# Connectors.net
KiCad netlist of a schematic drawn in Altium Designer
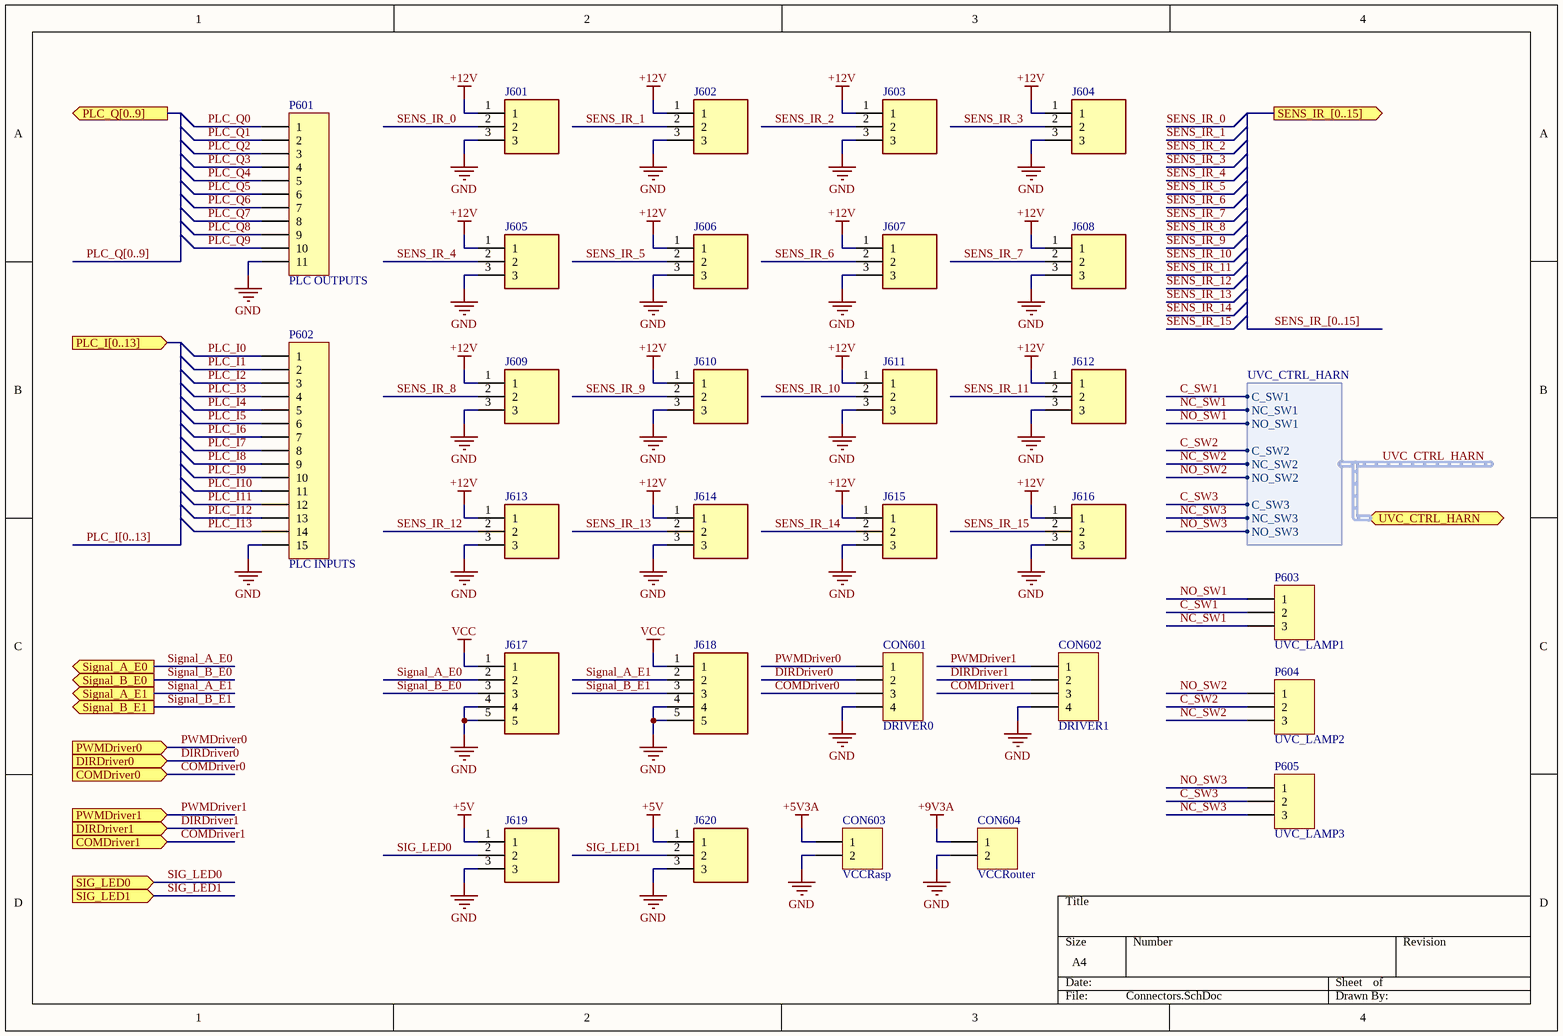
[diagram p0: Connectors.SchDoc]

(export (version "E")
  (design (tool "Eeschema 10.0.6"))
  (components
    (comp (ref "CON601")
      (value "Header PW4 - Recto")
      (footprint "PW4 - Recto")
      (description "Header PW - paso 0.156\"")
      (fields (field (name "VALOR") "DRIVER0"))
      (libsource (lib "RUF-Conectores") (part "Header PW4 - Recto"))
    )
    (comp (ref "CON602")
      (value "Header PW4 - Recto")
      (footprint "PW4 - Recto")
      (description "Header PW - paso 0.156\"")
      (fields (field (name "VALOR") "DRIVER1"))
      (libsource (lib "RUF-Conectores") (part "Header PW4 - Recto"))
    )
    (comp (ref "CON603")
      (value "Header PW2 - Recto")
      (footprint "PW2 - Recto")
      (description "Header PW - paso 0.156\"")
      (fields (field (name "VALOR") "VCCRasp"))
      (libsource (lib "RUF-Conectores") (part "Header PW2 - Recto"))
    )
    (comp (ref "CON604")
      (value "Header PW2 - Recto")
      (footprint "PW2 - Recto")
      (description "Header PW - paso 0.156\"")
      (fields (field (name "VALOR") "VCCRouter"))
      (libsource (lib "RUF-Conectores") (part "Header PW2 - Recto"))
    )
    (comp (ref "J601")
      (value "TBL002A-350-03GR-2OR")
      (footprint "CUI_TBL002A-350-03GR-2OR")
      (description "1~24 Poles, Screwless, 45°, 3.50 Pitch, 24~20 (AWG), Terminal Block Connector")
      (fields (field (name "MF") "CUI Devices"))
      (libsource (lib "TBL002A-350-03GR-2OR") (part "TBL002A-350-03GR-2OR"))
    )
    (comp (ref "J602")
      (value "TBL002A-350-03GR-2OR")
      (footprint "CUI_TBL002A-350-03GR-2OR")
      (description "1~24 Poles, Screwless, 45°, 3.50 Pitch, 24~20 (AWG), Terminal Block Connector")
      (fields (field (name "MF") "CUI Devices"))
      (libsource (lib "TBL002A-350-03GR-2OR") (part "TBL002A-350-03GR-2OR"))
    )
    (comp (ref "J603")
      (value "TBL002A-350-03GR-2OR")
      (footprint "CUI_TBL002A-350-03GR-2OR")
      (description "1~24 Poles, Screwless, 45°, 3.50 Pitch, 24~20 (AWG), Terminal Block Connector")
      (fields (field (name "MF") "CUI Devices"))
      (libsource (lib "TBL002A-350-03GR-2OR") (part "TBL002A-350-03GR-2OR"))
    )
    (comp (ref "J604")
      (value "TBL002A-350-03GR-2OR")
      (footprint "CUI_TBL002A-350-03GR-2OR")
      (description "1~24 Poles, Screwless, 45°, 3.50 Pitch, 24~20 (AWG), Terminal Block Connector")
      (fields (field (name "MF") "CUI Devices"))
      (libsource (lib "TBL002A-350-03GR-2OR") (part "TBL002A-350-03GR-2OR"))
    )
    (comp (ref "J605")
      (value "TBL002A-350-03GR-2OR")
      (footprint "CUI_TBL002A-350-03GR-2OR")
      (description "1~24 Poles, Screwless, 45°, 3.50 Pitch, 24~20 (AWG), Terminal Block Connector")
      (fields (field (name "MF") "CUI Devices"))
      (libsource (lib "TBL002A-350-03GR-2OR") (part "TBL002A-350-03GR-2OR"))
    )
    (comp (ref "J606")
      (value "TBL002A-350-03GR-2OR")
      (footprint "CUI_TBL002A-350-03GR-2OR")
      (description "1~24 Poles, Screwless, 45°, 3.50 Pitch, 24~20 (AWG), Terminal Block Connector")
      (fields (field (name "MF") "CUI Devices"))
      (libsource (lib "TBL002A-350-03GR-2OR") (part "TBL002A-350-03GR-2OR"))
    )
    (comp (ref "J607")
      (value "TBL002A-350-03GR-2OR")
      (footprint "CUI_TBL002A-350-03GR-2OR")
      (description "1~24 Poles, Screwless, 45°, 3.50 Pitch, 24~20 (AWG), Terminal Block Connector")
      (fields (field (name "MF") "CUI Devices"))
      (libsource (lib "TBL002A-350-03GR-2OR") (part "TBL002A-350-03GR-2OR"))
    )
    (comp (ref "J608")
      (value "TBL002A-350-03GR-2OR")
      (footprint "CUI_TBL002A-350-03GR-2OR")
      (description "1~24 Poles, Screwless, 45°, 3.50 Pitch, 24~20 (AWG), Terminal Block Connector")
      (fields (field (name "MF") "CUI Devices"))
      (libsource (lib "TBL002A-350-03GR-2OR") (part "TBL002A-350-03GR-2OR"))
    )
    (comp (ref "J609")
      (value "TBL002A-350-03GR-2OR")
      (footprint "CUI_TBL002A-350-03GR-2OR")
      (description "1~24 Poles, Screwless, 45°, 3.50 Pitch, 24~20 (AWG), Terminal Block Connector")
      (fields (field (name "MF") "CUI Devices"))
      (libsource (lib "TBL002A-350-03GR-2OR") (part "TBL002A-350-03GR-2OR"))
    )
    (comp (ref "J610")
      (value "TBL002A-350-03GR-2OR")
      (footprint "CUI_TBL002A-350-03GR-2OR")
      (description "1~24 Poles, Screwless, 45°, 3.50 Pitch, 24~20 (AWG), Terminal Block Connector")
      (fields (field (name "MF") "CUI Devices"))
      (libsource (lib "TBL002A-350-03GR-2OR") (part "TBL002A-350-03GR-2OR"))
    )
    (comp (ref "J611")
      (value "TBL002A-350-03GR-2OR")
      (footprint "CUI_TBL002A-350-03GR-2OR")
      (description "1~24 Poles, Screwless, 45°, 3.50 Pitch, 24~20 (AWG), Terminal Block Connector")
      (fields (field (name "MF") "CUI Devices"))
      (libsource (lib "TBL002A-350-03GR-2OR") (part "TBL002A-350-03GR-2OR"))
    )
    (comp (ref "J612")
      (value "TBL002A-350-03GR-2OR")
      (footprint "CUI_TBL002A-350-03GR-2OR")
      (description "1~24 Poles, Screwless, 45°, 3.50 Pitch, 24~20 (AWG), Terminal Block Connector")
      (fields (field (name "MF") "CUI Devices"))
      (libsource (lib "TBL002A-350-03GR-2OR") (part "TBL002A-350-03GR-2OR"))
    )
    (comp (ref "J613")
      (value "TBL002A-350-03GR-2OR")
      (footprint "CUI_TBL002A-350-03GR-2OR")
      (description "1~24 Poles, Screwless, 45°, 3.50 Pitch, 24~20 (AWG), Terminal Block Connector")
      (fields (field (name "MF") "CUI Devices"))
      (libsource (lib "TBL002A-350-03GR-2OR") (part "TBL002A-350-03GR-2OR"))
    )
    (comp (ref "J614")
      (value "TBL002A-350-03GR-2OR")
      (footprint "CUI_TBL002A-350-03GR-2OR")
      (description "1~24 Poles, Screwless, 45°, 3.50 Pitch, 24~20 (AWG), Terminal Block Connector")
      (fields (field (name "MF") "CUI Devices"))
      (libsource (lib "TBL002A-350-03GR-2OR") (part "TBL002A-350-03GR-2OR"))
    )
    (comp (ref "J615")
      (value "TBL002A-350-03GR-2OR")
      (footprint "CUI_TBL002A-350-03GR-2OR")
      (description "1~24 Poles, Screwless, 45°, 3.50 Pitch, 24~20 (AWG), Terminal Block Connector")
      (fields (field (name "MF") "CUI Devices"))
      (libsource (lib "TBL002A-350-03GR-2OR") (part "TBL002A-350-03GR-2OR"))
    )
    (comp (ref "J616")
      (value "TBL002A-350-03GR-2OR")
      (footprint "CUI_TBL002A-350-03GR-2OR")
      (description "1~24 Poles, Screwless, 45°, 3.50 Pitch, 24~20 (AWG), Terminal Block Connector")
      (fields (field (name "MF") "CUI Devices"))
      (libsource (lib "TBL002A-350-03GR-2OR") (part "TBL002A-350-03GR-2OR"))
    )
    (comp (ref "J617")
      (value "TBL002A-350-05GR-2OR")
      (footprint "CUI_TBL002A-350-05GR-2OR")
      (description "1~24 Poles, Screwless, 45°, 3.50 Pitch, 24~20 (AWG), Terminal Block Connector")
      (fields (field (name "MF") "CUI Devices"))
      (libsource (lib "TBL002A-350-05GR-2OR") (part "TBL002A-350-05GR-2OR"))
    )
    (comp (ref "J618")
      (value "TBL002A-350-05GR-2OR")
      (footprint "CUI_TBL002A-350-05GR-2OR")
      (description "1~24 Poles, Screwless, 45°, 3.50 Pitch, 24~20 (AWG), Terminal Block Connector")
      (fields (field (name "MF") "CUI Devices"))
      (libsource (lib "TBL002A-350-05GR-2OR") (part "TBL002A-350-05GR-2OR"))
    )
    (comp (ref "J619")
      (value "TBL002A-350-03GR-2OR")
      (footprint "CUI_TBL002A-350-03GR-2OR")
      (description "1~24 Poles, Screwless, 45°, 3.50 Pitch, 24~20 (AWG), Terminal Block Connector")
      (fields (field (name "MF") "CUI Devices"))
      (libsource (lib "TBL002A-350-03GR-2OR") (part "TBL002A-350-03GR-2OR"))
    )
    (comp (ref "J620")
      (value "TBL002A-350-03GR-2OR")
      (footprint "CUI_TBL002A-350-03GR-2OR")
      (description "1~24 Poles, Screwless, 45°, 3.50 Pitch, 24~20 (AWG), Terminal Block Connector")
      (fields (field (name "MF") "CUI Devices"))
      (libsource (lib "TBL002A-350-03GR-2OR") (part "TBL002A-350-03GR-2OR"))
    )
    (comp (ref "P601")
      (value "PLC OUTPUTS")
      (footprint "SPTAF_1/15-3.5-EL_11POS")
      (description "Header, 11-Pin")
      (fields (field (name "PUBLISHER") "Altium Limited"))
      (libsource (lib "Miscellaneous Connectors") (part "Header 11"))
    )
    (comp (ref "P602")
      (value "PLC INPUTS")
      (footprint "SPTAF_1/15-3.5-EL_15POS")
      (description "Header, 15-Pin")
      (fields (field (name "PUBLISHER") "Altium Limited"))
      (libsource (lib "Miscellaneous Connectors") (part "Header 15"))
    )
    (comp (ref "P603")
      (value "UVC_LAMP1")
      (footprint "Terminal_3way_508")
      (description "Header, 3-Pin")
      (fields (field (name "PUBLISHER") "Altium Limited"))
      (libsource (lib "Miscellaneous Connectors") (part "Header 3"))
    )
    (comp (ref "P604")
      (value "UVC_LAMP2")
      (footprint "Terminal_3way_508")
      (description "Header, 3-Pin")
      (fields (field (name "PUBLISHER") "Altium Limited"))
      (libsource (lib "Miscellaneous Connectors") (part "Header 3"))
    )
    (comp (ref "P605")
      (value "UVC_LAMP3")
      (footprint "Terminal_3way_508")
      (description "Header, 3-Pin")
      (fields (field (name "PUBLISHER") "Altium Limited"))
      (libsource (lib "Miscellaneous Connectors") (part "Header 3"))
    )
  )
  (nets
    (net (code "2") (name "+5V") (class "Default")
      (node (ref "J619") (pin "1") (pinfunction "1_1") (pintype "passive"))
      (node (ref "J620") (pin "1") (pinfunction "1_1") (pintype "passive"))
    )
    (net (code "3") (name "+5V3A") (class "Default")
      (node (ref "CON603") (pin "1") (pinfunction "1_1") (pintype "passive"))
    )
    (net (code "4") (name "+9V3A") (class "Default")
      (node (ref "CON604") (pin "1") (pinfunction "1_1") (pintype "passive"))
    )
    (net (code "5") (name "+12V") (class "Default")
      (node (ref "J601") (pin "1") (pinfunction "1_1") (pintype "passive"))
      (node (ref "J602") (pin "1") (pinfunction "1_1") (pintype "passive"))
      (node (ref "J603") (pin "1") (pinfunction "1_1") (pintype "passive"))
      (node (ref "J604") (pin "1") (pinfunction "1_1") (pintype "passive"))
      (node (ref "J605") (pin "1") (pinfunction "1_1") (pintype "passive"))
      (node (ref "J606") (pin "1") (pinfunction "1_1") (pintype "passive"))
      (node (ref "J607") (pin "1") (pinfunction "1_1") (pintype "passive"))
      (node (ref "J608") (pin "1") (pinfunction "1_1") (pintype "passive"))
      (node (ref "J609") (pin "1") (pinfunction "1_1") (pintype "passive"))
      (node (ref "J610") (pin "1") (pinfunction "1_1") (pintype "passive"))
      (node (ref "J611") (pin "1") (pinfunction "1_1") (pintype "passive"))
      (node (ref "J612") (pin "1") (pinfunction "1_1") (pintype "passive"))
      (node (ref "J613") (pin "1") (pinfunction "1_1") (pintype "passive"))
      (node (ref "J614") (pin "1") (pinfunction "1_1") (pintype "passive"))
      (node (ref "J615") (pin "1") (pinfunction "1_1") (pintype "passive"))
      (node (ref "J616") (pin "1") (pinfunction "1_1") (pintype "passive"))
    )
    (net (code "6") (name "/COMDriver0") (class "Default")
      (node (ref "CON601") (pin "3") (pinfunction "3_3") (pintype "passive"))
    )
    (net (code "7") (name "/COMDriver1") (class "Default")
      (node (ref "CON602") (pin "3") (pinfunction "3_3") (pintype "passive"))
    )
    (net (code "8") (name "/C_SW1") (class "Default")
      (node (ref "P603") (pin "2") (pinfunction "2_2") (pintype "passive"))
    )
    (net (code "9") (name "/C_SW2") (class "Default")
      (node (ref "P604") (pin "2") (pinfunction "2_2") (pintype "passive"))
    )
    (net (code "10") (name "/C_SW3") (class "Default")
      (node (ref "P605") (pin "2") (pinfunction "2_2") (pintype "passive"))
    )
    (net (code "11") (name "/DIRDriver0") (class "Default")
      (node (ref "CON601") (pin "2") (pinfunction "2_2") (pintype "passive"))
    )
    (net (code "12") (name "/DIRDriver1") (class "Default")
      (node (ref "CON602") (pin "2") (pinfunction "2_2") (pintype "passive"))
    )
    (net (code "13") (name "/NC_SW1") (class "Default")
      (node (ref "P603") (pin "3") (pinfunction "3_3") (pintype "passive"))
    )
    (net (code "14") (name "/NC_SW2") (class "Default")
      (node (ref "P604") (pin "3") (pinfunction "3_3") (pintype "passive"))
    )
    (net (code "15") (name "/NC_SW3") (class "Default")
      (node (ref "P605") (pin "3") (pinfunction "3_3") (pintype "passive"))
    )
    (net (code "16") (name "/NO_SW1") (class "Default")
      (node (ref "P603") (pin "1") (pinfunction "1_1") (pintype "passive"))
    )
    (net (code "17") (name "/NO_SW2") (class "Default")
      (node (ref "P604") (pin "1") (pinfunction "1_1") (pintype "passive"))
    )
    (net (code "18") (name "/NO_SW3") (class "Default")
      (node (ref "P605") (pin "1") (pinfunction "1_1") (pintype "passive"))
    )
    (net (code "19") (name "/PLC_I0") (class "Default")
      (node (ref "P602") (pin "1") (pinfunction "1_1") (pintype "passive"))
    )
    (net (code "20") (name "/PLC_I1") (class "Default")
      (node (ref "P602") (pin "2") (pinfunction "2_2") (pintype "passive"))
    )
    (net (code "21") (name "/PLC_I2") (class "Default")
      (node (ref "P602") (pin "3") (pinfunction "3_3") (pintype "passive"))
    )
    (net (code "22") (name "/PLC_I3") (class "Default")
      (node (ref "P602") (pin "4") (pinfunction "4_4") (pintype "passive"))
    )
    (net (code "23") (name "/PLC_I4") (class "Default")
      (node (ref "P602") (pin "5") (pinfunction "5_5") (pintype "passive"))
    )
    (net (code "24") (name "/PLC_I5") (class "Default")
      (node (ref "P602") (pin "6") (pinfunction "6_6") (pintype "passive"))
    )
    (net (code "25") (name "/PLC_I6") (class "Default")
      (node (ref "P602") (pin "7") (pinfunction "7_7") (pintype "passive"))
    )
    (net (code "26") (name "/PLC_I7") (class "Default")
      (node (ref "P602") (pin "8") (pinfunction "8_8") (pintype "passive"))
    )
    (net (code "27") (name "/PLC_I8") (class "Default")
      (node (ref "P602") (pin "9") (pinfunction "9_9") (pintype "passive"))
    )
    (net (code "28") (name "/PLC_I9") (class "Default")
      (node (ref "P602") (pin "10") (pinfunction "10_10") (pintype "passive"))
    )
    (net (code "29") (name "/PLC_I10") (class "Default")
      (node (ref "P602") (pin "11") (pinfunction "11_11") (pintype "passive"))
    )
    (net (code "30") (name "/PLC_I11") (class "Default")
      (node (ref "P602") (pin "12") (pinfunction "12_12") (pintype "passive"))
    )
    (net (code "31") (name "/PLC_I12") (class "Default")
      (node (ref "P602") (pin "13") (pinfunction "13_13") (pintype "passive"))
    )
    (net (code "32") (name "/PLC_I13") (class "Default")
      (node (ref "P602") (pin "14") (pinfunction "14_14") (pintype "passive"))
    )
    (net (code "34") (name "/PLC_Q0") (class "Default")
      (node (ref "P601") (pin "1") (pinfunction "1_1") (pintype "passive"))
    )
    (net (code "35") (name "/PLC_Q1") (class "Default")
      (node (ref "P601") (pin "2") (pinfunction "2_2") (pintype "passive"))
    )
    (net (code "36") (name "/PLC_Q2") (class "Default")
      (node (ref "P601") (pin "3") (pinfunction "3_3") (pintype "passive"))
    )
    (net (code "37") (name "/PLC_Q3") (class "Default")
      (node (ref "P601") (pin "4") (pinfunction "4_4") (pintype "passive"))
    )
    (net (code "38") (name "/PLC_Q4") (class "Default")
      (node (ref "P601") (pin "5") (pinfunction "5_5") (pintype "passive"))
    )
    (net (code "39") (name "/PLC_Q5") (class "Default")
      (node (ref "P601") (pin "6") (pinfunction "6_6") (pintype "passive"))
    )
    (net (code "40") (name "/PLC_Q6") (class "Default")
      (node (ref "P601") (pin "7") (pinfunction "7_7") (pintype "passive"))
    )
    (net (code "41") (name "/PLC_Q7") (class "Default")
      (node (ref "P601") (pin "8") (pinfunction "8_8") (pintype "passive"))
    )
    (net (code "42") (name "/PLC_Q8") (class "Default")
      (node (ref "P601") (pin "9") (pinfunction "9_9") (pintype "passive"))
    )
    (net (code "43") (name "/PLC_Q9") (class "Default")
      (node (ref "P601") (pin "10") (pinfunction "10_10") (pintype "passive"))
    )
    (net (code "45") (name "/PWMDriver0") (class "Default")
      (node (ref "CON601") (pin "1") (pinfunction "1_1") (pintype "passive"))
    )
    (net (code "46") (name "/PWMDriver1") (class "Default")
      (node (ref "CON602") (pin "1") (pinfunction "1_1") (pintype "passive"))
    )
    (net (code "47") (name "/SENS_IR_0") (class "Default")
      (node (ref "J601") (pin "2") (pinfunction "2_2") (pintype "passive"))
    )
    (net (code "48") (name "/SENS_IR_1") (class "Default")
      (node (ref "J602") (pin "2") (pinfunction "2_2") (pintype "passive"))
    )
    (net (code "49") (name "/SENS_IR_2") (class "Default")
      (node (ref "J603") (pin "2") (pinfunction "2_2") (pintype "passive"))
    )
    (net (code "50") (name "/SENS_IR_3") (class "Default")
      (node (ref "J604") (pin "2") (pinfunction "2_2") (pintype "passive"))
    )
    (net (code "51") (name "/SENS_IR_4") (class "Default")
      (node (ref "J605") (pin "2") (pinfunction "2_2") (pintype "passive"))
    )
    (net (code "52") (name "/SENS_IR_5") (class "Default")
      (node (ref "J606") (pin "2") (pinfunction "2_2") (pintype "passive"))
    )
    (net (code "53") (name "/SENS_IR_6") (class "Default")
      (node (ref "J607") (pin "2") (pinfunction "2_2") (pintype "passive"))
    )
    (net (code "54") (name "/SENS_IR_7") (class "Default")
      (node (ref "J608") (pin "2") (pinfunction "2_2") (pintype "passive"))
    )
    (net (code "55") (name "/SENS_IR_8") (class "Default")
      (node (ref "J609") (pin "2") (pinfunction "2_2") (pintype "passive"))
    )
    (net (code "56") (name "/SENS_IR_9") (class "Default")
      (node (ref "J610") (pin "2") (pinfunction "2_2") (pintype "passive"))
    )
    (net (code "57") (name "/SENS_IR_10") (class "Default")
      (node (ref "J611") (pin "2") (pinfunction "2_2") (pintype "passive"))
    )
    (net (code "58") (name "/SENS_IR_11") (class "Default")
      (node (ref "J612") (pin "2") (pinfunction "2_2") (pintype "passive"))
    )
    (net (code "59") (name "/SENS_IR_12") (class "Default")
      (node (ref "J613") (pin "2") (pinfunction "2_2") (pintype "passive"))
    )
    (net (code "60") (name "/SENS_IR_13") (class "Default")
      (node (ref "J614") (pin "2") (pinfunction "2_2") (pintype "passive"))
    )
    (net (code "61") (name "/SENS_IR_14") (class "Default")
      (node (ref "J615") (pin "2") (pinfunction "2_2") (pintype "passive"))
    )
    (net (code "62") (name "/SENS_IR_15") (class "Default")
      (node (ref "J616") (pin "2") (pinfunction "2_2") (pintype "passive"))
    )
    (net (code "64") (name "/SIG_LED0") (class "Default")
      (node (ref "J619") (pin "2") (pinfunction "2_2") (pintype "passive"))
    )
    (net (code "65") (name "/SIG_LED1") (class "Default")
      (node (ref "J620") (pin "2") (pinfunction "2_2") (pintype "passive"))
    )
    (net (code "66") (name "/Signal_A_E0") (class "Default")
      (node (ref "J617") (pin "2") (pinfunction "2_2") (pintype "passive"))
    )
    (net (code "67") (name "/Signal_A_E1") (class "Default")
      (node (ref "J618") (pin "2") (pinfunction "2_2") (pintype "passive"))
    )
    (net (code "68") (name "/Signal_B_E0") (class "Default")
      (node (ref "J617") (pin "3") (pinfunction "3_3") (pintype "passive"))
    )
    (net (code "69") (name "/Signal_B_E1") (class "Default")
      (node (ref "J618") (pin "3") (pinfunction "3_3") (pintype "passive"))
    )
    (net (code "71") (name "GND") (class "Default")
      (node (ref "CON601") (pin "4") (pinfunction "4_4") (pintype "passive"))
      (node (ref "CON602") (pin "4") (pinfunction "4_4") (pintype "passive"))
      (node (ref "CON603") (pin "2") (pinfunction "2_2") (pintype "passive"))
      (node (ref "CON604") (pin "2") (pinfunction "2_2") (pintype "passive"))
      (node (ref "J601") (pin "3") (pinfunction "3_3") (pintype "passive"))
      (node (ref "J602") (pin "3") (pinfunction "3_3") (pintype "passive"))
      (node (ref "J603") (pin "3") (pinfunction "3_3") (pintype "passive"))
      (node (ref "J604") (pin "3") (pinfunction "3_3") (pintype "passive"))
      (node (ref "J605") (pin "3") (pinfunction "3_3") (pintype "passive"))
      (node (ref "J606") (pin "3") (pinfunction "3_3") (pintype "passive"))
      (node (ref "J607") (pin "3") (pinfunction "3_3") (pintype "passive"))
      (node (ref "J608") (pin "3") (pinfunction "3_3") (pintype "passive"))
      (node (ref "J609") (pin "3") (pinfunction "3_3") (pintype "passive"))
      (node (ref "J610") (pin "3") (pinfunction "3_3") (pintype "passive"))
      (node (ref "J611") (pin "3") (pinfunction "3_3") (pintype "passive"))
      (node (ref "J612") (pin "3") (pinfunction "3_3") (pintype "passive"))
      (node (ref "J613") (pin "3") (pinfunction "3_3") (pintype "passive"))
      (node (ref "J614") (pin "3") (pinfunction "3_3") (pintype "passive"))
      (node (ref "J615") (pin "3") (pinfunction "3_3") (pintype "passive"))
      (node (ref "J616") (pin "3") (pinfunction "3_3") (pintype "passive"))
      (node (ref "J617") (pin "4") (pinfunction "4_4") (pintype "passive"))
      (node (ref "J617") (pin "5") (pinfunction "5_5") (pintype "passive"))
      (node (ref "J618") (pin "4") (pinfunction "4_4") (pintype "passive"))
      (node (ref "J618") (pin "5") (pinfunction "5_5") (pintype "passive"))
      (node (ref "J619") (pin "3") (pinfunction "3_3") (pintype "passive"))
      (node (ref "J620") (pin "3") (pinfunction "3_3") (pintype "passive"))
      (node (ref "P601") (pin "11") (pinfunction "11_11") (pintype "passive"))
      (node (ref "P602") (pin "15") (pinfunction "15_15") (pintype "passive"))
    )
    (net (code "72") (name "VCC") (class "Default")
      (node (ref "J617") (pin "1") (pinfunction "1_1") (pintype "passive"))
      (node (ref "J618") (pin "1") (pinfunction "1_1") (pintype "passive"))
    )
  )
)
